# ppLight.net
KiCad netlist of a schematic drawn in EAGLE
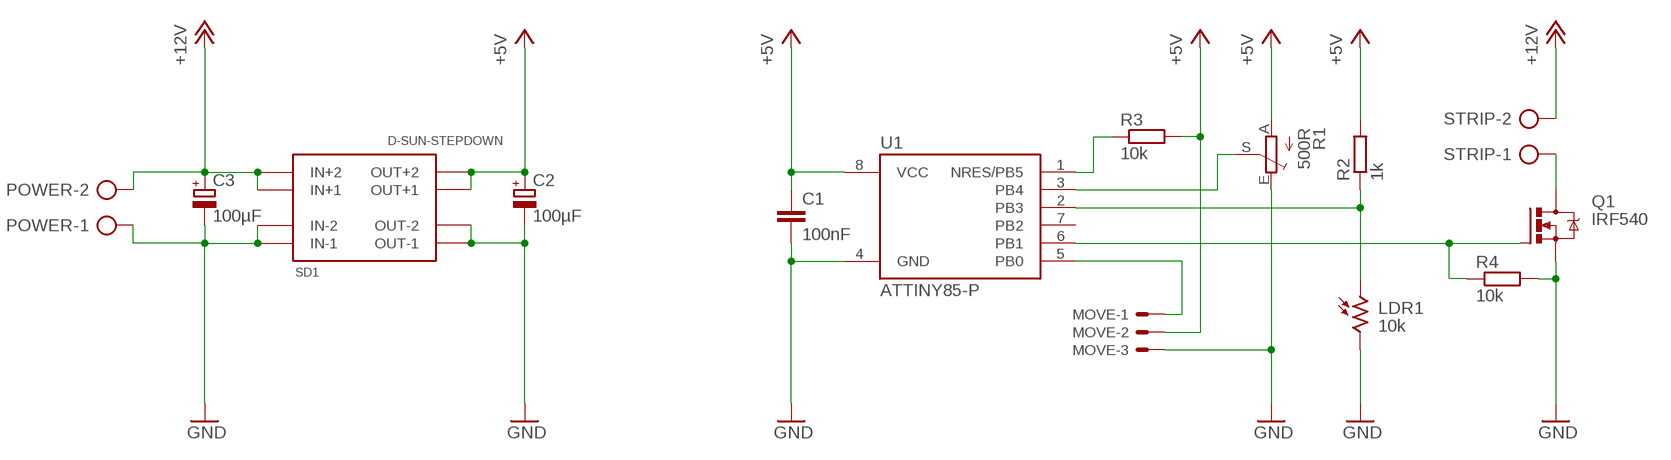
[diagram p0: schematic, sheet 1]

(export (version "E")
  (design (tool "Eeschema 10.0.6"))
  (components
    (comp (ref "C1")
      (value "100nF")
      (footprint "eagle-import:C025-025X050")
      (libsource (lib "eagle-import") (part "C-EU025-025X050"))
    )
    (comp (ref "C2")
      (value "100µF")
      (footprint "eagle-import:E2,5-5")
      (libsource (lib "eagle-import") (part "CPOL-EUE2.5-5"))
    )
    (comp (ref "C3")
      (value "100µF")
      (footprint "eagle-import:E2,5-5")
      (libsource (lib "eagle-import") (part "CPOL-EUE2.5-5"))
    )
    (comp (ref "LDR1")
      (value "10k")
      (footprint "eagle-import:VT900")
      (libsource (lib "eagle-import") (part "VT90N1"))
    )
    (comp (ref "MOVE")
      (value "22-05-7038-03")
      (footprint "eagle-import:7395-03")
      (libsource (lib "eagle-import") (part "22-?-0305-7038"))
    )
    (comp (ref "POWER")
      (value "AK500/2")
      (footprint "eagle-import:AK500_2")
      (libsource (lib "eagle-import") (part "AK500/2"))
    )
    (comp (ref "Q1")
      (value "IRF540")
      (footprint "eagle-import:TO220BV")
      (libsource (lib "eagle-import") (part "IRF540"))
    )
    (comp (ref "R1")
      (value "500R")
      (footprint "eagle-import:CT6")
      (libsource (lib "eagle-import") (part "TRIM_EU-CT6"))
    )
    (comp (ref "R2")
      (value "1k")
      (footprint "eagle-import:0204_7")
      (libsource (lib "eagle-import") (part "R-EU_0204/7"))
    )
    (comp (ref "R3")
      (value "10k")
      (footprint "eagle-import:0204_7")
      (libsource (lib "eagle-import") (part "R-EU_0204/7"))
    )
    (comp (ref "R4")
      (value "10k")
      (footprint "eagle-import:0204_7")
      (libsource (lib "eagle-import") (part "R-EU_0204/7"))
    )
    (comp (ref "SD1")
      (value "D-SUN-STEPDOWN")
      (footprint "eagle-import:STEPDOWN-21X16")
      (libsource (lib "eagle-import") (part "D-SUN-STEPDOWN"))
    )
    (comp (ref "STRIP")
      (value "AK500/2")
      (footprint "eagle-import:AK500_2")
      (libsource (lib "eagle-import") (part "AK500/2"))
    )
    (comp (ref "U1")
      (value "ATTINY85-P")
      (footprint "eagle-import:PDIP08_300MIL")
      (libsource (lib "eagle-import") (part "ATTINY85P-"))
    )
  )
  (nets
    (net (code "1") (name "+5V") (class "Default")
      (node (ref "C1") (pin "1") (pinfunction "1_1") (pintype "passive"))
      (node (ref "C2") (pin "+") (pinfunction "+_+") (pintype "passive"))
      (node (ref "MOVE") (pin "2") (pinfunction "S_2") (pintype "passive"))
      (node (ref "R1") (pin "A") (pinfunction "A_A") (pintype "passive"))
      (node (ref "R2") (pin "2") (pinfunction "2_2") (pintype "passive"))
      (node (ref "R3") (pin "2") (pinfunction "2_2") (pintype "passive"))
      (node (ref "SD1") (pin "OUT+1") (pinfunction "OUT+1_OUT+1") (pintype "power_in"))
      (node (ref "SD1") (pin "OUT+2") (pinfunction "OUT+2_OUT+2") (pintype "power_in"))
      (node (ref "U1") (pin "8") (pinfunction "VCC_8") (pintype "power_in"))
    )
    (net (code "2") (name "+12V") (class "Default")
      (node (ref "C3") (pin "+") (pinfunction "+_+") (pintype "passive"))
      (node (ref "POWER") (pin "2") (pinfunction "KL_2") (pintype "passive"))
      (node (ref "SD1") (pin "IN+1") (pinfunction "IN+1_IN+1") (pintype "power_in"))
      (node (ref "SD1") (pin "IN+2") (pinfunction "IN+2_IN+2") (pintype "power_in"))
      (node (ref "STRIP") (pin "2") (pinfunction "KL_2") (pintype "passive"))
    )
    (net (code "3") (name "GND") (class "Default")
      (node (ref "C1") (pin "2") (pinfunction "2_2") (pintype "passive"))
      (node (ref "C2") (pin "-") (pinfunction "-_-") (pintype "passive"))
      (node (ref "C3") (pin "-") (pinfunction "-_-") (pintype "passive"))
      (node (ref "LDR1") (pin "2") (pinfunction "2_2") (pintype "passive"))
      (node (ref "MOVE") (pin "3") (pinfunction "S_3") (pintype "passive"))
      (node (ref "POWER") (pin "1") (pinfunction "KL_1") (pintype "passive"))
      (node (ref "Q1") (pin "S") (pinfunction "S_S") (pintype "passive"))
      (node (ref "R1") (pin "E") (pinfunction "E_E") (pintype "passive"))
      (node (ref "R4") (pin "2") (pinfunction "2_2") (pintype "passive"))
      (node (ref "SD1") (pin "IN-1") (pinfunction "IN-1_IN-1") (pintype "power_in"))
      (node (ref "SD1") (pin "IN-2") (pinfunction "IN-2_IN-2") (pintype "power_in"))
      (node (ref "SD1") (pin "OUT-1") (pinfunction "OUT-1_OUT-1") (pintype "power_in"))
      (node (ref "SD1") (pin "OUT-2") (pinfunction "OUT-2_OUT-2") (pintype "power_in"))
      (node (ref "U1") (pin "4") (pinfunction "GND_4") (pintype "power_in"))
    )
    (net (code "4") (name "Net-(MOVEA-S)") (class "Default")
      (node (ref "MOVE") (pin "1") (pinfunction "S_1") (pintype "passive"))
      (node (ref "U1") (pin "5") (pinfunction "PB0_5") (pintype "bidirectional"))
    )
    (net (code "5") (name "Net-(STRIPA-KL)") (class "Default")
      (node (ref "Q1") (pin "D") (pinfunction "D_D") (pintype "passive"))
      (node (ref "STRIP") (pin "1") (pinfunction "KL_1") (pintype "passive"))
    )
    (net (code "6") (name "Net-(U1-NRES{slash}PB5)") (class "Default")
      (node (ref "R3") (pin "1") (pinfunction "1_1") (pintype "passive"))
      (node (ref "U1") (pin "1") (pinfunction "NRES/PB5_1") (pintype "bidirectional"))
    )
    (net (code "7") (name "Net-(U1-PB1)") (class "Default")
      (node (ref "Q1") (pin "G") (pinfunction "G_G") (pintype "passive"))
      (node (ref "R4") (pin "1") (pinfunction "1_1") (pintype "passive"))
      (node (ref "U1") (pin "6") (pinfunction "PB1_6") (pintype "bidirectional"))
    )
    (net (code "8") (name "Net-(U1-PB3)") (class "Default")
      (node (ref "LDR1") (pin "1") (pinfunction "1_1") (pintype "passive"))
      (node (ref "R2") (pin "1") (pinfunction "1_1") (pintype "passive"))
      (node (ref "U1") (pin "2") (pinfunction "PB3_2") (pintype "bidirectional"))
    )
    (net (code "9") (name "Net-(U1-PB4)") (class "Default")
      (node (ref "R1") (pin "S") (pinfunction "S_S") (pintype "passive"))
      (node (ref "U1") (pin "3") (pinfunction "PB4_3") (pintype "bidirectional"))
    )
    (net (code "10") (name "unconnected-(U1-PB2-Pad7)") (class "Default")
      (node (ref "U1") (pin "7") (pinfunction "PB2_7") (pintype "bidirectional"))
    )
  )
)
